# 2_Control.net
KiCad netlist of a schematic drawn in Altium Designer
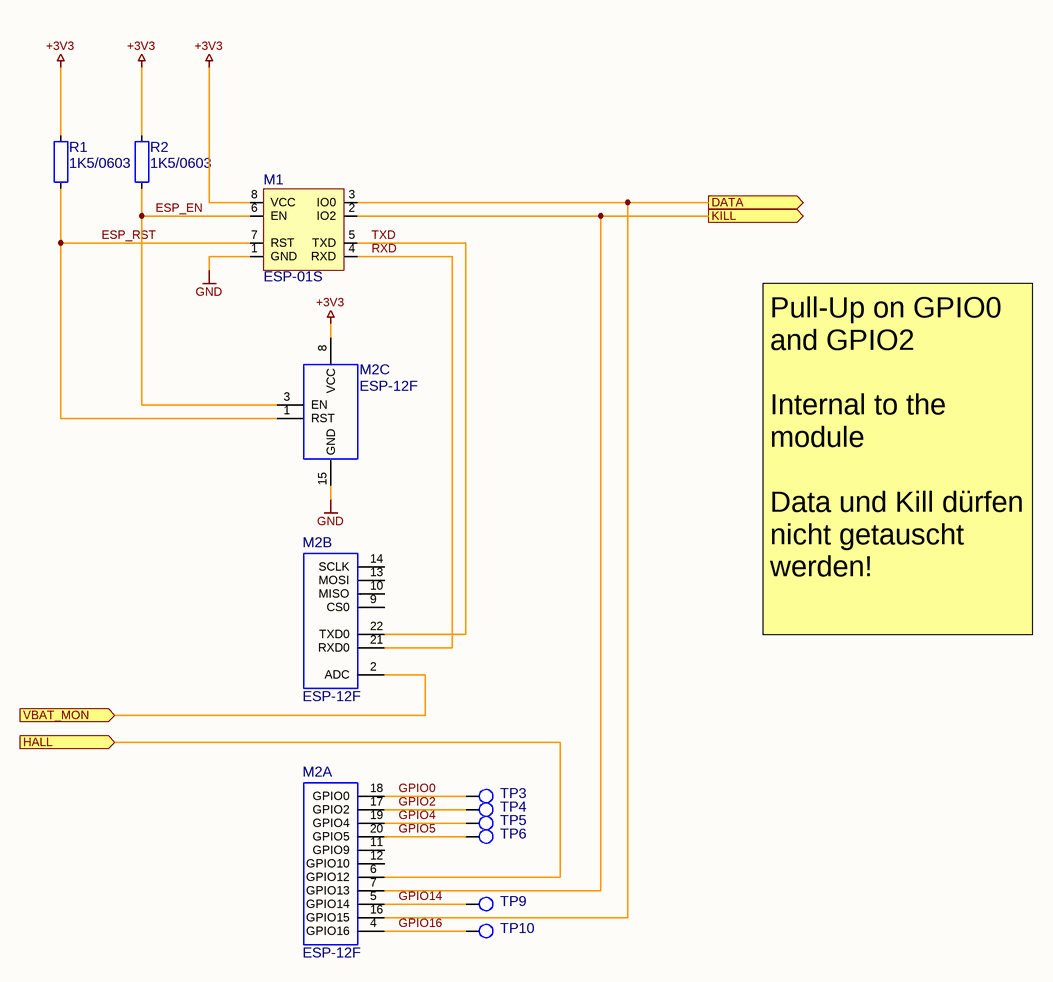
[diagram p0: [2] Control.SchDoc]

(export (version "E")
  (design (tool "Eeschema 10.0.6"))
  (components
    (comp (ref "M1")
      (value "ESP-01S")
      (footprint "ESP-01S")
      (description "ESP8266 based Module with 1MByte Storage")
      (fields (field (name "MANUFACTURER") "AI-Thinker"))
      (libsource (lib "daniw_altium_lib") (part "ESP-01S"))
    )
    (comp (ref "M2")
      (value "ESP-12F")
      (footprint "ESP-12F")
      (description "ESP8266 based Module with 4MByte Storage")
      (fields (field (name "MANUFACTURER") "AI-Thinker"))
      (libsource (lib "daniw_altium_lib") (part "ESP-12F"))
    )
    (comp (ref "R1")
      (value "1K5/0603")
      (footprint "R0603-0.40-WW")
      (description "RES SM 0603 1K5")
      (fields (field (name "MANUFACTURER") "GENERIC"))
      (libsource (lib "daniw_altium_lib") (part "R"))
    )
    (comp (ref "R2")
      (value "1K5/0603")
      (footprint "R0603-0.40-WW")
      (description "RES SM 0603 1K5")
      (fields (field (name "MANUFACTURER") "GENERIC"))
      (libsource (lib "daniw_altium_lib") (part "R"))
    )
    (comp (ref "TP3")
      (value "TP_THD_1.5/0.8")
      (footprint "TP_THD_1.5/0.8")
      (description "THT Test Point 1.5/0.8mm")
      (fields (field (name "MANUFACTURER") "NONE"))
      (libsource (lib "daniw_altium_lib") (part "Testpoint"))
    )
    (comp (ref "TP4")
      (value "TP_THD_1.5/0.8")
      (footprint "TP_THD_1.5/0.8")
      (description "THT Test Point 1.5/0.8mm")
      (fields (field (name "MANUFACTURER") "NONE"))
      (libsource (lib "daniw_altium_lib") (part "Testpoint"))
    )
    (comp (ref "TP5")
      (value "TP_THD_1.5/0.8")
      (footprint "TP_THD_1.5/0.8")
      (description "THT Test Point 1.5/0.8mm")
      (fields (field (name "MANUFACTURER") "NONE"))
      (libsource (lib "daniw_altium_lib") (part "Testpoint"))
    )
    (comp (ref "TP6")
      (value "TP_THD_1.5/0.8")
      (footprint "TP_THD_1.5/0.8")
      (description "THT Test Point 1.5/0.8mm")
      (fields (field (name "MANUFACTURER") "NONE"))
      (libsource (lib "daniw_altium_lib") (part "Testpoint"))
    )
    (comp (ref "TP9")
      (value "TP_THD_1.5/0.8")
      (footprint "TP_THD_1.5/0.8")
      (description "THT Test Point 1.5/0.8mm")
      (fields (field (name "MANUFACTURER") "NONE"))
      (libsource (lib "daniw_altium_lib") (part "Testpoint"))
    )
    (comp (ref "TP10")
      (value "TP_THD_1.5/0.8")
      (footprint "TP_THD_1.5/0.8")
      (description "THT Test Point 1.5/0.8mm")
      (fields (field (name "MANUFACTURER") "NONE"))
      (libsource (lib "daniw_altium_lib") (part "Testpoint"))
    )
  )
  (nets
    (net (code "1") (name "+3V3") (class "Default")
      (node (ref "M1") (pin "8") (pinfunction "VCC_8") (pintype "passive"))
      (node (ref "M2") (pin "8") (pinfunction "VCC_8") (pintype "passive"))
      (node (ref "R1") (pin "1") (pinfunction "1_1") (pintype "passive"))
      (node (ref "R2") (pin "1") (pinfunction "1_1") (pintype "passive"))
    )
    (net (code "2") (name "/DATA") (class "Default")
      (node (ref "M1") (pin "3") (pinfunction "IO0_3") (pintype "passive"))
      (node (ref "M2") (pin "16") (pinfunction "GPIO15_16") (pintype "passive"))
    )
    (net (code "3") (name "/ESP_EN") (class "Default")
      (node (ref "M1") (pin "6") (pinfunction "EN_6") (pintype "passive"))
      (node (ref "M2") (pin "3") (pinfunction "EN_3") (pintype "passive"))
      (node (ref "R2") (pin "2") (pinfunction "2_2") (pintype "passive"))
    )
    (net (code "4") (name "/ESP_RST") (class "Default")
      (node (ref "M1") (pin "7") (pinfunction "RST_7") (pintype "passive"))
      (node (ref "M2") (pin "1") (pinfunction "RST_1") (pintype "passive"))
      (node (ref "R1") (pin "2") (pinfunction "2_2") (pintype "passive"))
    )
    (net (code "5") (name "/GPIO0") (class "Default")
      (node (ref "M2") (pin "18") (pinfunction "GPIO0_18") (pintype "passive"))
      (node (ref "TP3") (pin "1") (pinfunction "1_1") (pintype "passive"))
    )
    (net (code "6") (name "/GPIO2") (class "Default")
      (node (ref "M2") (pin "17") (pinfunction "GPIO2_17") (pintype "passive"))
      (node (ref "TP4") (pin "1") (pinfunction "1_1") (pintype "passive"))
    )
    (net (code "7") (name "/GPIO4") (class "Default")
      (node (ref "M2") (pin "19") (pinfunction "GPIO4_19") (pintype "passive"))
      (node (ref "TP5") (pin "1") (pinfunction "1_1") (pintype "passive"))
    )
    (net (code "8") (name "/GPIO5") (class "Default")
      (node (ref "M2") (pin "20") (pinfunction "GPIO5_20") (pintype "passive"))
      (node (ref "TP6") (pin "1") (pinfunction "1_1") (pintype "passive"))
    )
    (net (code "9") (name "/GPIO14") (class "Default")
      (node (ref "M2") (pin "5") (pinfunction "GPIO14_5") (pintype "passive"))
      (node (ref "TP9") (pin "1") (pinfunction "1_1") (pintype "passive"))
    )
    (net (code "10") (name "/GPIO16") (class "Default")
      (node (ref "M2") (pin "4") (pinfunction "GPIO16_4") (pintype "passive"))
      (node (ref "TP10") (pin "1") (pinfunction "1_1") (pintype "passive"))
    )
    (net (code "11") (name "/HALL") (class "Default")
      (node (ref "M2") (pin "6") (pinfunction "GPIO12_6") (pintype "passive"))
    )
    (net (code "12") (name "/KILL") (class "Default")
      (node (ref "M1") (pin "2") (pinfunction "IO2_2") (pintype "passive"))
      (node (ref "M2") (pin "7") (pinfunction "GPIO13_7") (pintype "passive"))
    )
    (net (code "13") (name "/RXD") (class "Default")
      (node (ref "M1") (pin "4") (pinfunction "RXD_4") (pintype "passive"))
      (node (ref "M2") (pin "21") (pinfunction "RXD0_21") (pintype "passive"))
    )
    (net (code "14") (name "/TXD") (class "Default")
      (node (ref "M1") (pin "5") (pinfunction "TXD_5") (pintype "passive"))
      (node (ref "M2") (pin "22") (pinfunction "TXD0_22") (pintype "passive"))
    )
    (net (code "15") (name "/VBAT_MON") (class "Default")
      (node (ref "M2") (pin "2") (pinfunction "ADC_2") (pintype "passive"))
    )
    (net (code "16") (name "GND") (class "Default")
      (node (ref "M1") (pin "1") (pinfunction "GND_1") (pintype "passive"))
      (node (ref "M2") (pin "15") (pinfunction "GND_15") (pintype "passive"))
    )
    (net (code "17") (name "unconnected-(M2A-GPIO9-Pad11)") (class "Default")
      (node (ref "M2") (pin "11") (pinfunction "GPIO9_11") (pintype "passive"))
    )
    (net (code "18") (name "unconnected-(M2A-GPIO10-Pad12)") (class "Default")
      (node (ref "M2") (pin "12") (pinfunction "GPIO10_12") (pintype "passive"))
    )
    (net (code "19") (name "unconnected-(M2B-CS0-Pad9)") (class "Default")
      (node (ref "M2") (pin "9") (pinfunction "CS0_9") (pintype "passive"))
    )
    (net (code "20") (name "unconnected-(M2B-MISO-Pad10)") (class "Default")
      (node (ref "M2") (pin "10") (pinfunction "MISO_10") (pintype "passive"))
    )
    (net (code "21") (name "unconnected-(M2B-MOSI-Pad13)") (class "Default")
      (node (ref "M2") (pin "13") (pinfunction "MOSI_13") (pintype "passive"))
    )
    (net (code "22") (name "unconnected-(M2B-SCLK-Pad14)") (class "Default")
      (node (ref "M2") (pin "14") (pinfunction "SCLK_14") (pintype "passive"))
    )
  )
)
